# BD3721X_DUAL.net
KiCad netlist of a schematic drawn in EAGLE
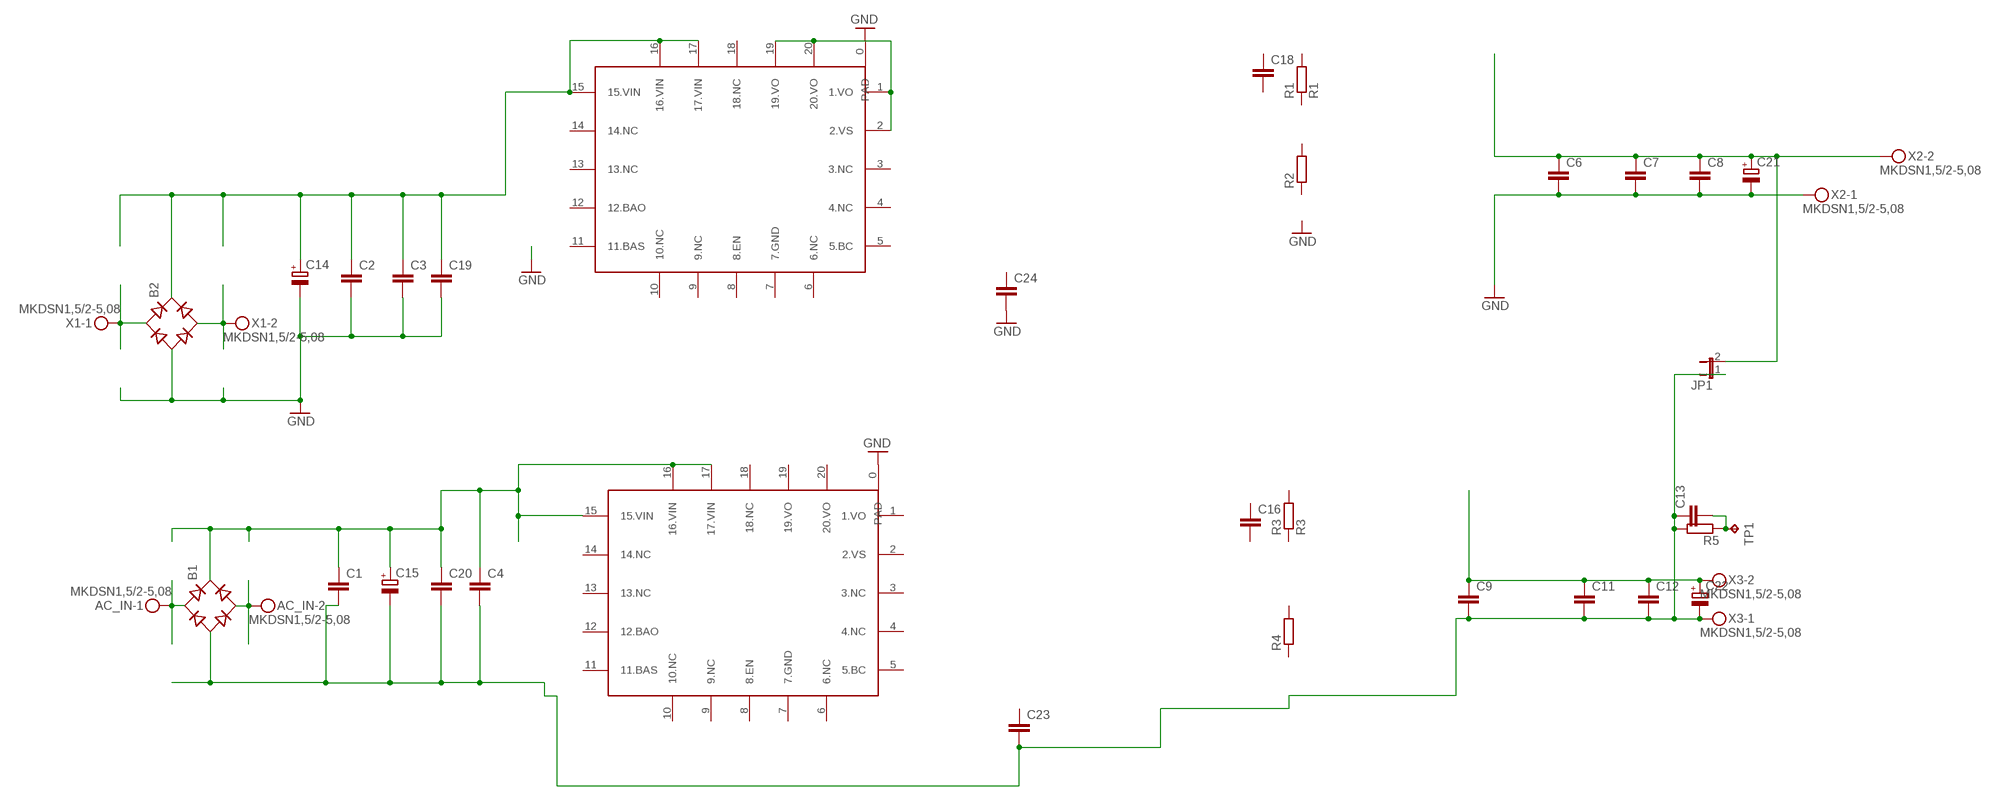
[diagram p0: schematic, sheet 1]

(export (version "E")
  (design (tool "Eeschema 10.0.6"))
  (components
    (comp (ref "AC_IN")
      (value "MKDSN1,5/2-5,08")
      (footprint "eagle-import:MKDSN1,5_2-5,08")
      (libsource (lib "eagle-import") (part "MKDSN1,5/2-5,08"))
    )
    (comp (ref "B1")
      (value "RB1A")
      (footprint "eagle-import:RB1A")
      (libsource (lib "eagle-import") (part "RB1A"))
    )
    (comp (ref "B2")
      (value "RB1A")
      (footprint "eagle-import:RB1A")
      (libsource (lib "eagle-import") (part "RB1A"))
    )
    (comp (ref "C1")
      (value "C-EUC1210")
      (footprint "eagle-import:C1210")
      (libsource (lib "eagle-import") (part "C-EUC1210"))
    )
    (comp (ref "C2")
      (value "C-EUC1210")
      (footprint "eagle-import:C1210")
      (libsource (lib "eagle-import") (part "C-EUC1210"))
    )
    (comp (ref "C3")
      (value "C-EUC0805")
      (footprint "eagle-import:C0805")
      (libsource (lib "eagle-import") (part "C-EUC0805"))
    )
    (comp (ref "C4")
      (value "C-EUC0805")
      (footprint "eagle-import:C0805")
      (libsource (lib "eagle-import") (part "C-EUC0805"))
    )
    (comp (ref "C6")
      (value "C-EUC0603")
      (footprint "eagle-import:C0603")
      (libsource (lib "eagle-import") (part "C-EUC0603"))
    )
    (comp (ref "C7")
      (value "C-EUC0805")
      (footprint "eagle-import:C0805")
      (libsource (lib "eagle-import") (part "C-EUC0805"))
    )
    (comp (ref "C8")
      (value "C-EUC1210")
      (footprint "eagle-import:C1210")
      (libsource (lib "eagle-import") (part "C-EUC1210"))
    )
    (comp (ref "C9")
      (value "C-EUC0603")
      (footprint "eagle-import:C0603")
      (libsource (lib "eagle-import") (part "C-EUC0603"))
    )
    (comp (ref "C11")
      (value "C-EUC1210")
      (footprint "eagle-import:C1210")
      (libsource (lib "eagle-import") (part "C-EUC1210"))
    )
    (comp (ref "C12")
      (value "C-EUC0805")
      (footprint "eagle-import:C0805")
      (libsource (lib "eagle-import") (part "C-EUC0805"))
    )
    (comp (ref "C13")
      (value "C-EU075-042X103")
      (footprint "eagle-import:C075-042X103")
      (libsource (lib "eagle-import") (part "C-EU075-042X103"))
    )
    (comp (ref "C14")
      (value "CPOL-EUE5-13")
      (footprint "eagle-import:E5-13")
      (libsource (lib "eagle-import") (part "CPOL-EUE5-13"))
    )
    (comp (ref "C15")
      (value "CPOL-EUE5-13")
      (footprint "eagle-import:E5-13")
      (libsource (lib "eagle-import") (part "CPOL-EUE5-13"))
    )
    (comp (ref "C16")
      (value "C-EUC0603")
      (footprint "eagle-import:C0603")
      (libsource (lib "eagle-import") (part "C-EUC0603"))
    )
    (comp (ref "C18")
      (value "C-EUC0603")
      (footprint "eagle-import:C0603")
      (libsource (lib "eagle-import") (part "C-EUC0603"))
    )
    (comp (ref "C19")
      (value "C-EUC0603")
      (footprint "eagle-import:C0603")
      (libsource (lib "eagle-import") (part "C-EUC0603"))
    )
    (comp (ref "C20")
      (value "C-EUC0603")
      (footprint "eagle-import:C0603")
      (libsource (lib "eagle-import") (part "C-EUC0603"))
    )
    (comp (ref "C21")
      (value "CPOL-EUE3.5-8")
      (footprint "eagle-import:E3,5-8")
      (libsource (lib "eagle-import") (part "CPOL-EUE3.5-8"))
    )
    (comp (ref "C22")
      (value "CPOL-EUE3.5-8")
      (footprint "eagle-import:E3,5-8")
      (libsource (lib "eagle-import") (part "CPOL-EUE3.5-8"))
    )
    (comp (ref "C23")
      (value "C-EUC0603")
      (footprint "eagle-import:C0603")
      (libsource (lib "eagle-import") (part "C-EUC0603"))
    )
    (comp (ref "C24")
      (value "C-EUC0603")
      (footprint "eagle-import:C0603")
      (libsource (lib "eagle-import") (part "C-EUC0603"))
    )
    (comp (ref "JP1")
      (value "JP1E")
      (footprint "eagle-import:JP1")
      (libsource (lib "eagle-import") (part "JP1E"))
    )
    (comp (ref "R1")
      (value "R1")
      (footprint "eagle-import:R0805")
      (libsource (lib "eagle-import") (part "R-EU_R0805"))
    )
    (comp (ref "R2")
      (value "R-EU_R0805")
      (footprint "eagle-import:R0805")
      (libsource (lib "eagle-import") (part "R-EU_R0805"))
    )
    (comp (ref "R3")
      (value "R3")
      (footprint "eagle-import:R0805")
      (libsource (lib "eagle-import") (part "R-EU_R0805"))
    )
    (comp (ref "R4")
      (value "R-EU_R0805")
      (footprint "eagle-import:R0805")
      (libsource (lib "eagle-import") (part "R-EU_R0805"))
    )
    (comp (ref "R5")
      (value "R-EU_0207/12")
      (footprint "eagle-import:0207_12")
      (libsource (lib "eagle-import") (part "R-EU_0207/12"))
    )
    (comp (ref "TP1")
      (value "TPPAD1-13")
      (footprint "eagle-import:P1-13")
      (libsource (lib "eagle-import") (part "TPPAD1-13"))
    )
    (comp (ref "U$1")
      (value "BD37210QFN20")
      (footprint "eagle-import:QFN20-4X4MM")
      (libsource (lib "eagle-import") (part "BD37210QFN20"))
    )
    (comp (ref "U$2")
      (value "BD37210QFN20")
      (footprint "eagle-import:QFN20-4X4MM")
      (libsource (lib "eagle-import") (part "BD37210QFN20"))
    )
    (comp (ref "X1")
      (value "MKDSN1,5/2-5,08")
      (footprint "eagle-import:MKDSN1,5_2-5,08")
      (libsource (lib "eagle-import") (part "MKDSN1,5/2-5,08"))
    )
    (comp (ref "X2")
      (value "MKDSN1,5/2-5,08")
      (footprint "eagle-import:MKDSN1,5_2-5,08")
      (libsource (lib "eagle-import") (part "MKDSN1,5/2-5,08"))
    )
    (comp (ref "X3")
      (value "MKDSN1,5/2-5,08")
      (footprint "eagle-import:MKDSN1,5_2-5,08")
      (libsource (lib "eagle-import") (part "MKDSN1,5/2-5,08"))
    )
  )
  (nets
    (net (code "1") (name "GND") (class "Default")
      (node (ref "B2") (pin "-") (pinfunction "-_-") (pintype "passive"))
      (node (ref "C14") (pin "-") (pinfunction "-_-") (pintype "passive"))
      (node (ref "C19") (pin "2") (pinfunction "2_2") (pintype "passive"))
      (node (ref "C2") (pin "2") (pinfunction "2_2") (pintype "passive"))
      (node (ref "C21") (pin "-") (pinfunction "-_-") (pintype "passive"))
      (node (ref "C24") (pin "2") (pinfunction "2_2") (pintype "passive"))
      (node (ref "C3") (pin "2") (pinfunction "2_2") (pintype "passive"))
      (node (ref "C6") (pin "2") (pinfunction "2_2") (pintype "passive"))
      (node (ref "C7") (pin "2") (pinfunction "2_2") (pintype "passive"))
      (node (ref "C8") (pin "2") (pinfunction "2_2") (pintype "passive"))
      (node (ref "U$1") (pin "0") (pinfunction "PAD_0") (pintype "bidirectional"))
      (node (ref "U$2") (pin "0") (pinfunction "PAD_0") (pintype "bidirectional"))
      (node (ref "X2") (pin "1") (pinfunction "KL_1") (pintype "passive"))
    )
    (net (code "2") (name "Net-(AC_INA-KL)") (class "Default")
      (node (ref "AC_IN") (pin "1") (pinfunction "KL_1") (pintype "passive"))
      (node (ref "B1") (pin "AC1") (pinfunction "AC1_AC1") (pintype "passive"))
    )
    (net (code "3") (name "Net-(AC_INB-KL)") (class "Default")
      (node (ref "AC_IN") (pin "2") (pinfunction "KL_2") (pintype "passive"))
      (node (ref "B1") (pin "AC2") (pinfunction "AC2_AC2") (pintype "passive"))
    )
    (net (code "4") (name "Net-(C13-Pad2)") (class "Default")
      (node (ref "C13") (pin "2") (pinfunction "2_2") (pintype "passive"))
      (node (ref "R5") (pin "1") (pinfunction "1_1") (pintype "passive"))
      (node (ref "TP1") (pin "TP") (pinfunction "TP_TP") (pintype "input"))
    )
    (net (code "5") (name "Net-(U$1-1.VO)") (class "Default")
      (node (ref "U$1") (pin "1") (pinfunction "1.VO_1") (pintype "bidirectional"))
      (node (ref "U$1") (pin "19") (pinfunction "19.VO_19") (pintype "bidirectional"))
      (node (ref "U$1") (pin "2") (pinfunction "2.VS_2") (pintype "bidirectional"))
      (node (ref "U$1") (pin "20") (pinfunction "20.VO_20") (pintype "bidirectional"))
    )
    (net (code "6") (name "Net-(U$1-15.VIN)") (class "Default")
      (node (ref "B2") (pin "+") (pinfunction "+_+") (pintype "passive"))
      (node (ref "C14") (pin "+") (pinfunction "+_+") (pintype "passive"))
      (node (ref "C19") (pin "1") (pinfunction "1_1") (pintype "passive"))
      (node (ref "C2") (pin "1") (pinfunction "1_1") (pintype "passive"))
      (node (ref "C3") (pin "1") (pinfunction "1_1") (pintype "passive"))
      (node (ref "U$1") (pin "15") (pinfunction "15.VIN_15") (pintype "bidirectional"))
      (node (ref "U$1") (pin "16") (pinfunction "16.VIN_16") (pintype "bidirectional"))
      (node (ref "U$1") (pin "17") (pinfunction "17.VIN_17") (pintype "bidirectional"))
    )
    (net (code "7") (name "Net-(U$2-15.VIN)") (class "Default")
      (node (ref "B1") (pin "+") (pinfunction "+_+") (pintype "passive"))
      (node (ref "C1") (pin "1") (pinfunction "1_1") (pintype "passive"))
      (node (ref "C15") (pin "+") (pinfunction "+_+") (pintype "passive"))
      (node (ref "C20") (pin "1") (pinfunction "1_1") (pintype "passive"))
      (node (ref "C4") (pin "1") (pinfunction "1_1") (pintype "passive"))
      (node (ref "U$2") (pin "15") (pinfunction "15.VIN_15") (pintype "bidirectional"))
      (node (ref "U$2") (pin "16") (pinfunction "16.VIN_16") (pintype "bidirectional"))
      (node (ref "U$2") (pin "17") (pinfunction "17.VIN_17") (pintype "bidirectional"))
    )
    (net (code "8") (name "Net-(X1A-KL)") (class "Default")
      (node (ref "B2") (pin "AC1") (pinfunction "AC1_AC1") (pintype "passive"))
      (node (ref "X1") (pin "1") (pinfunction "KL_1") (pintype "passive"))
    )
    (net (code "9") (name "Net-(X1B-KL)") (class "Default")
      (node (ref "B2") (pin "AC2") (pinfunction "AC2_AC2") (pintype "passive"))
      (node (ref "X1") (pin "2") (pinfunction "KL_2") (pintype "passive"))
    )
    (net (code "10") (name "Net-(X2B-KL)") (class "Default")
      (node (ref "C21") (pin "+") (pinfunction "+_+") (pintype "passive"))
      (node (ref "C6") (pin "1") (pinfunction "1_1") (pintype "passive"))
      (node (ref "C7") (pin "1") (pinfunction "1_1") (pintype "passive"))
      (node (ref "C8") (pin "1") (pinfunction "1_1") (pintype "passive"))
      (node (ref "JP1") (pin "2") (pinfunction "2_2") (pintype "passive"))
      (node (ref "X2") (pin "2") (pinfunction "KL_2") (pintype "passive"))
    )
    (net (code "11") (name "Net-(X3A-KL)") (class "Default")
      (node (ref "B1") (pin "-") (pinfunction "-_-") (pintype "passive"))
      (node (ref "C1") (pin "2") (pinfunction "2_2") (pintype "passive"))
      (node (ref "C11") (pin "2") (pinfunction "2_2") (pintype "passive"))
      (node (ref "C12") (pin "2") (pinfunction "2_2") (pintype "passive"))
      (node (ref "C13") (pin "1") (pinfunction "1_1") (pintype "passive"))
      (node (ref "C15") (pin "-") (pinfunction "-_-") (pintype "passive"))
      (node (ref "C20") (pin "2") (pinfunction "2_2") (pintype "passive"))
      (node (ref "C22") (pin "-") (pinfunction "-_-") (pintype "passive"))
      (node (ref "C23") (pin "2") (pinfunction "2_2") (pintype "passive"))
      (node (ref "C4") (pin "2") (pinfunction "2_2") (pintype "passive"))
      (node (ref "C9") (pin "2") (pinfunction "2_2") (pintype "passive"))
      (node (ref "JP1") (pin "1") (pinfunction "1_1") (pintype "passive"))
      (node (ref "R5") (pin "2") (pinfunction "2_2") (pintype "passive"))
      (node (ref "X3") (pin "1") (pinfunction "KL_1") (pintype "passive"))
    )
    (net (code "12") (name "Net-(X3B-KL)") (class "Default")
      (node (ref "C11") (pin "1") (pinfunction "1_1") (pintype "passive"))
      (node (ref "C12") (pin "1") (pinfunction "1_1") (pintype "passive"))
      (node (ref "C22") (pin "+") (pinfunction "+_+") (pintype "passive"))
      (node (ref "C9") (pin "1") (pinfunction "1_1") (pintype "passive"))
      (node (ref "X3") (pin "2") (pinfunction "KL_2") (pintype "passive"))
    )
    (net (code "13") (name "unconnected-(C16-Pad1)") (class "Default")
      (node (ref "C16") (pin "1") (pinfunction "1_1") (pintype "passive"))
    )
    (net (code "14") (name "unconnected-(C16-Pad2)") (class "Default")
      (node (ref "C16") (pin "2") (pinfunction "2_2") (pintype "passive"))
    )
    (net (code "15") (name "unconnected-(C18-Pad1)") (class "Default")
      (node (ref "C18") (pin "1") (pinfunction "1_1") (pintype "passive"))
    )
    (net (code "16") (name "unconnected-(C18-Pad2)") (class "Default")
      (node (ref "C18") (pin "2") (pinfunction "2_2") (pintype "passive"))
    )
    (net (code "17") (name "unconnected-(C23-Pad1)") (class "Default")
      (node (ref "C23") (pin "1") (pinfunction "1_1") (pintype "passive"))
    )
    (net (code "18") (name "unconnected-(C24-Pad1)") (class "Default")
      (node (ref "C24") (pin "1") (pinfunction "1_1") (pintype "passive"))
    )
    (net (code "19") (name "unconnected-(R1-Pad1)") (class "Default")
      (node (ref "R1") (pin "1") (pinfunction "1_1") (pintype "passive"))
    )
    (net (code "20") (name "unconnected-(R1-Pad2)") (class "Default")
      (node (ref "R1") (pin "2") (pinfunction "2_2") (pintype "passive"))
    )
    (net (code "21") (name "unconnected-(R2-Pad1)") (class "Default")
      (node (ref "R2") (pin "1") (pinfunction "1_1") (pintype "passive"))
    )
    (net (code "22") (name "unconnected-(R2-Pad2)") (class "Default")
      (node (ref "R2") (pin "2") (pinfunction "2_2") (pintype "passive"))
    )
    (net (code "23") (name "unconnected-(R3-Pad1)") (class "Default")
      (node (ref "R3") (pin "1") (pinfunction "1_1") (pintype "passive"))
    )
    (net (code "24") (name "unconnected-(R3-Pad2)") (class "Default")
      (node (ref "R3") (pin "2") (pinfunction "2_2") (pintype "passive"))
    )
    (net (code "25") (name "unconnected-(R4-Pad1)") (class "Default")
      (node (ref "R4") (pin "1") (pinfunction "1_1") (pintype "passive"))
    )
    (net (code "26") (name "unconnected-(R4-Pad2)") (class "Default")
      (node (ref "R4") (pin "2") (pinfunction "2_2") (pintype "passive"))
    )
    (net (code "27") (name "unconnected-(U$1-3.NC-Pad3)") (class "Default")
      (node (ref "U$1") (pin "3") (pinfunction "3.NC_3") (pintype "bidirectional"))
    )
    (net (code "28") (name "unconnected-(U$1-4.NC-Pad4)") (class "Default")
      (node (ref "U$1") (pin "4") (pinfunction "4.NC_4") (pintype "bidirectional"))
    )
    (net (code "29") (name "unconnected-(U$1-5.BC-Pad5)") (class "Default")
      (node (ref "U$1") (pin "5") (pinfunction "5.BC_5") (pintype "bidirectional"))
    )
    (net (code "30") (name "unconnected-(U$1-6.NC-Pad6)") (class "Default")
      (node (ref "U$1") (pin "6") (pinfunction "6.NC_6") (pintype "bidirectional"))
    )
    (net (code "31") (name "unconnected-(U$1-7.GND-Pad7)") (class "Default")
      (node (ref "U$1") (pin "7") (pinfunction "7.GND_7") (pintype "bidirectional"))
    )
    (net (code "32") (name "unconnected-(U$1-8.EN-Pad8)") (class "Default")
      (node (ref "U$1") (pin "8") (pinfunction "8.EN_8") (pintype "bidirectional"))
    )
    (net (code "33") (name "unconnected-(U$1-9.NC-Pad9)") (class "Default")
      (node (ref "U$1") (pin "9") (pinfunction "9.NC_9") (pintype "bidirectional"))
    )
    (net (code "34") (name "unconnected-(U$1-10.NC-Pad10)") (class "Default")
      (node (ref "U$1") (pin "10") (pinfunction "10.NC_10") (pintype "bidirectional"))
    )
    (net (code "35") (name "unconnected-(U$1-11.BAS-Pad11)") (class "Default")
      (node (ref "U$1") (pin "11") (pinfunction "11.BAS_11") (pintype "bidirectional"))
    )
    (net (code "36") (name "unconnected-(U$1-12.BAO-Pad12)") (class "Default")
      (node (ref "U$1") (pin "12") (pinfunction "12.BAO_12") (pintype "bidirectional"))
    )
    (net (code "37") (name "unconnected-(U$1-13.NC-Pad13)") (class "Default")
      (node (ref "U$1") (pin "13") (pinfunction "13.NC_13") (pintype "bidirectional"))
    )
    (net (code "38") (name "unconnected-(U$1-14.NC-Pad14)") (class "Default")
      (node (ref "U$1") (pin "14") (pinfunction "14.NC_14") (pintype "bidirectional"))
    )
    (net (code "39") (name "unconnected-(U$1-18.NC-Pad18)") (class "Default")
      (node (ref "U$1") (pin "18") (pinfunction "18.NC_18") (pintype "bidirectional"))
    )
    (net (code "40") (name "unconnected-(U$2-1.VO-Pad1)") (class "Default")
      (node (ref "U$2") (pin "1") (pinfunction "1.VO_1") (pintype "bidirectional"))
    )
    (net (code "41") (name "unconnected-(U$2-2.VS-Pad2)") (class "Default")
      (node (ref "U$2") (pin "2") (pinfunction "2.VS_2") (pintype "bidirectional"))
    )
    (net (code "42") (name "unconnected-(U$2-3.NC-Pad3)") (class "Default")
      (node (ref "U$2") (pin "3") (pinfunction "3.NC_3") (pintype "bidirectional"))
    )
    (net (code "43") (name "unconnected-(U$2-4.NC-Pad4)") (class "Default")
      (node (ref "U$2") (pin "4") (pinfunction "4.NC_4") (pintype "bidirectional"))
    )
    (net (code "44") (name "unconnected-(U$2-5.BC-Pad5)") (class "Default")
      (node (ref "U$2") (pin "5") (pinfunction "5.BC_5") (pintype "bidirectional"))
    )
    (net (code "45") (name "unconnected-(U$2-6.NC-Pad6)") (class "Default")
      (node (ref "U$2") (pin "6") (pinfunction "6.NC_6") (pintype "bidirectional"))
    )
    (net (code "46") (name "unconnected-(U$2-7.GND-Pad7)") (class "Default")
      (node (ref "U$2") (pin "7") (pinfunction "7.GND_7") (pintype "bidirectional"))
    )
    (net (code "47") (name "unconnected-(U$2-8.EN-Pad8)") (class "Default")
      (node (ref "U$2") (pin "8") (pinfunction "8.EN_8") (pintype "bidirectional"))
    )
    (net (code "48") (name "unconnected-(U$2-9.NC-Pad9)") (class "Default")
      (node (ref "U$2") (pin "9") (pinfunction "9.NC_9") (pintype "bidirectional"))
    )
    (net (code "49") (name "unconnected-(U$2-10.NC-Pad10)") (class "Default")
      (node (ref "U$2") (pin "10") (pinfunction "10.NC_10") (pintype "bidirectional"))
    )
    (net (code "50") (name "unconnected-(U$2-11.BAS-Pad11)") (class "Default")
      (node (ref "U$2") (pin "11") (pinfunction "11.BAS_11") (pintype "bidirectional"))
    )
    (net (code "51") (name "unconnected-(U$2-12.BAO-Pad12)") (class "Default")
      (node (ref "U$2") (pin "12") (pinfunction "12.BAO_12") (pintype "bidirectional"))
    )
    (net (code "52") (name "unconnected-(U$2-13.NC-Pad13)") (class "Default")
      (node (ref "U$2") (pin "13") (pinfunction "13.NC_13") (pintype "bidirectional"))
    )
    (net (code "53") (name "unconnected-(U$2-14.NC-Pad14)") (class "Default")
      (node (ref "U$2") (pin "14") (pinfunction "14.NC_14") (pintype "bidirectional"))
    )
    (net (code "54") (name "unconnected-(U$2-18.NC-Pad18)") (class "Default")
      (node (ref "U$2") (pin "18") (pinfunction "18.NC_18") (pintype "bidirectional"))
    )
    (net (code "55") (name "unconnected-(U$2-19.VO-Pad19)") (class "Default")
      (node (ref "U$2") (pin "19") (pinfunction "19.VO_19") (pintype "bidirectional"))
    )
    (net (code "56") (name "unconnected-(U$2-20.VO-Pad20)") (class "Default")
      (node (ref "U$2") (pin "20") (pinfunction "20.VO_20") (pintype "bidirectional"))
    )
  )
)
